# CSS811_CO2_TVOC_Breakout.net
KiCad netlist of a schematic drawn in EAGLE
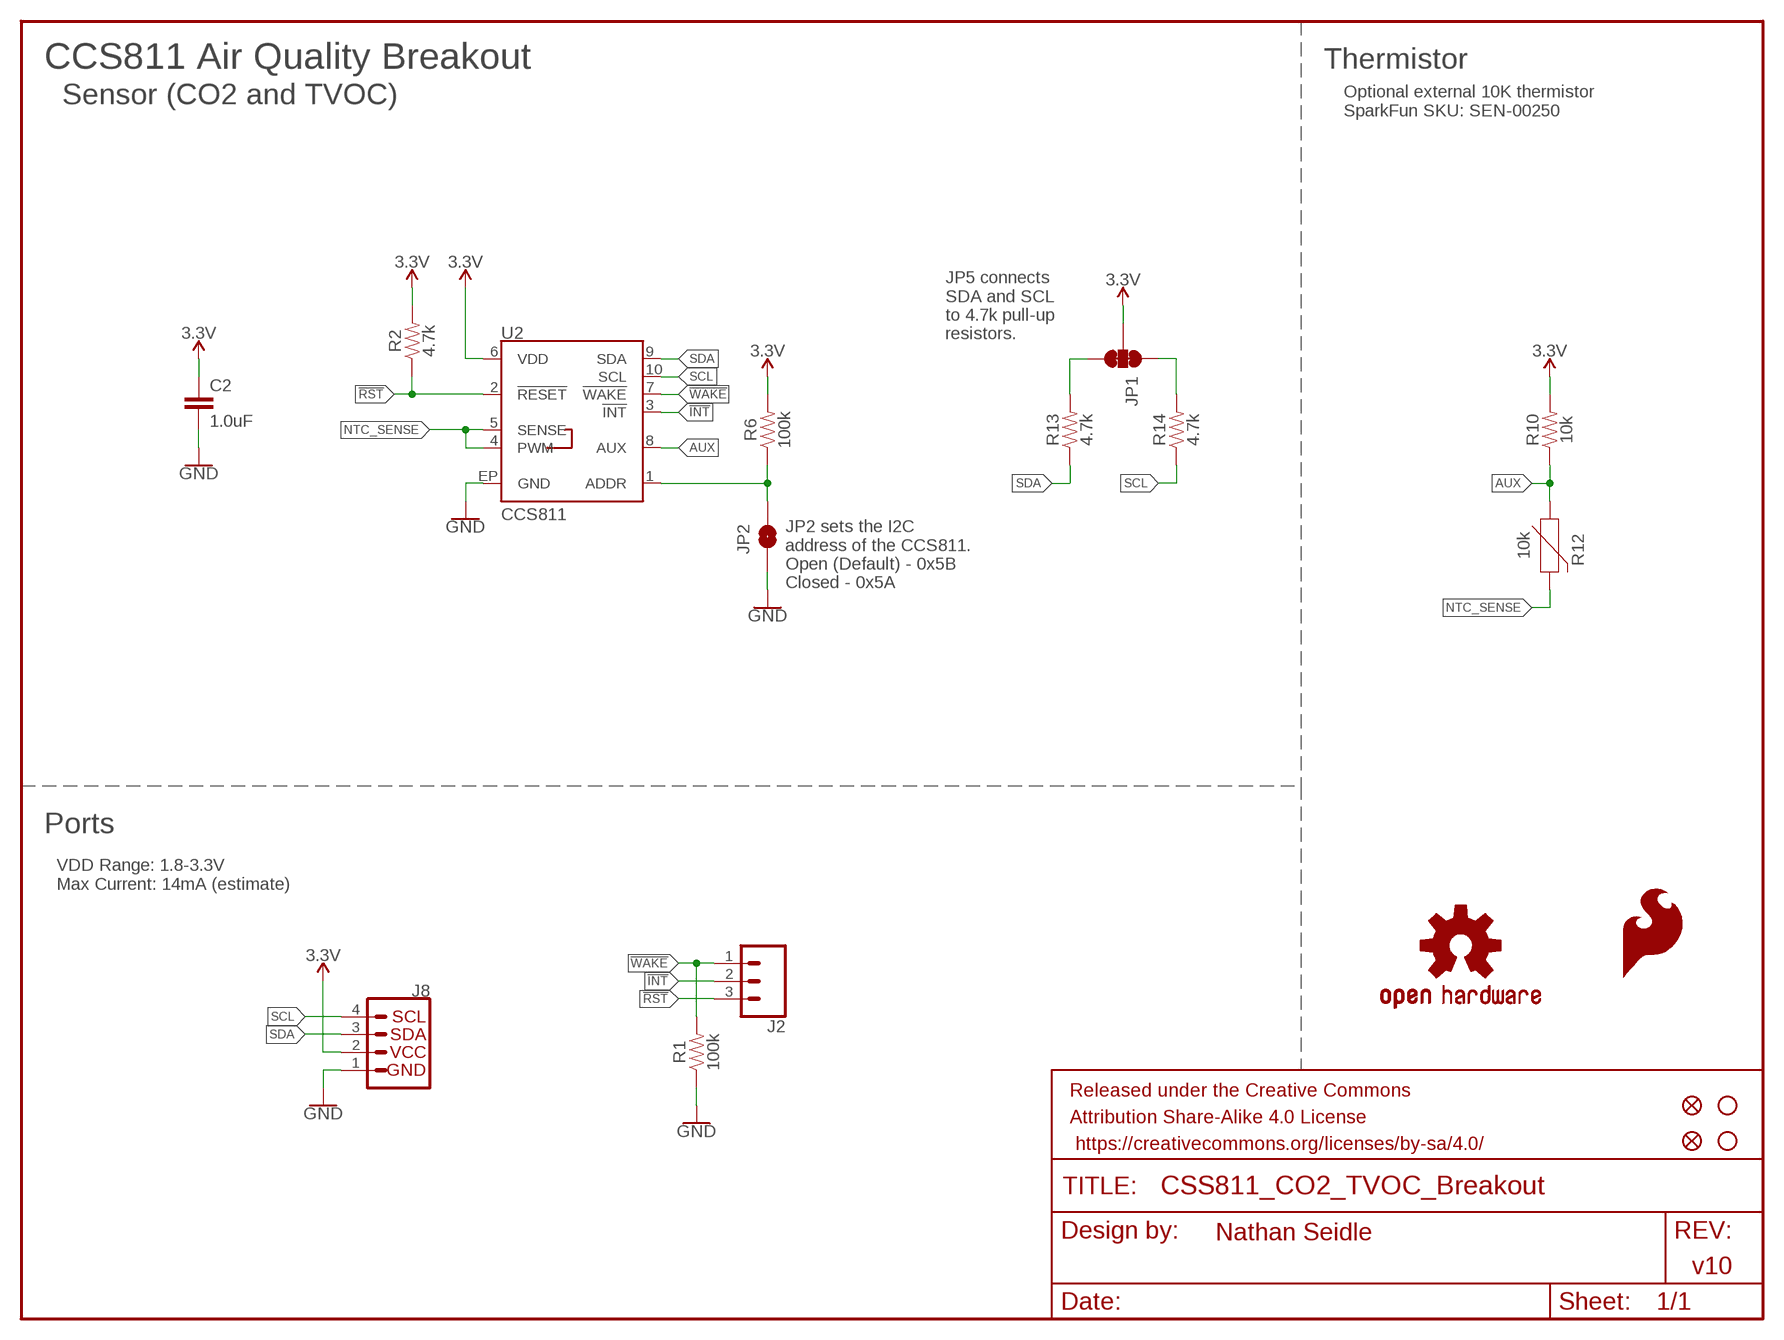
[diagram p0: schematic, sheet 1]

(export (version "E")
  (design (tool "Eeschema 10.0.6"))
  (components
    (comp (ref "C2")
      (value "1.0uF")
      (footprint "eagle-import:0603")
      (libsource (lib "eagle-import") (part "1.0UF-0603-16V-10%"))
    )
    (comp (ref "FD1")
      (value "FIDUCIAL1X2")
      (footprint "eagle-import:FIDUCIAL-1X2")
      (libsource (lib "eagle-import") (part "FIDUCIAL1X2"))
    )
    (comp (ref "FD2")
      (value "FIDUCIAL1X2")
      (footprint "eagle-import:FIDUCIAL-1X2")
      (libsource (lib "eagle-import") (part "FIDUCIAL1X2"))
    )
    (comp (ref "FRAME1")
      (value "FRAME-LETTER")
      (footprint "eagle-import:CREATIVE_COMMONS")
      (libsource (lib "eagle-import") (part "FRAME-LETTER"))
    )
    (comp (ref "H2")
      (value "STAND-OFF")
      (footprint "eagle-import:STAND-OFF")
      (libsource (lib "eagle-import") (part "STAND-OFF"))
    )
    (comp (ref "H4")
      (value "STAND-OFF")
      (footprint "eagle-import:STAND-OFF")
      (libsource (lib "eagle-import") (part "STAND-OFF"))
    )
    (comp (ref "J2")
      (value "CONN_031X03_NO_SILK")
      (footprint "eagle-import:1X03_NO_SILK")
      (libsource (lib "eagle-import") (part "CONN_031X03_NO_SILK"))
    )
    (comp (ref "J8")
      (value "I2C_STANDARD_NO_SILK")
      (footprint "eagle-import:1X04_NO_SILK")
      (libsource (lib "eagle-import") (part "I2C_STANDARD_NO_SILK"))
    )
    (comp (ref "JP1")
      (value "JUMPER-SMT_3_2-NC_TRACE_SILK")
      (footprint "eagle-import:SMT-JUMPER_3_2-NC_TRACE_SILK")
      (libsource (lib "eagle-import") (part "JUMPER-SMT_3_2-NC_TRACE_SILK"))
    )
    (comp (ref "JP2")
      (value "JUMPER-SMT_2_NO_SILK")
      (footprint "eagle-import:SMT-JUMPER_2_NO_SILK")
      (libsource (lib "eagle-import") (part "JUMPER-SMT_2_NO_SILK"))
    )
    (comp (ref "LOGO1")
      (value "SFE_LOGO_FLAME.2_INCH")
      (footprint "eagle-import:SFE_LOGO_FLAME_.2")
      (libsource (lib "eagle-import") (part "SFE_LOGO_FLAME.2_INCH"))
    )
    (comp (ref "LOGO4")
      (value "OSHW-LOGOS")
      (footprint "eagle-import:OSHW-LOGO-S")
      (libsource (lib "eagle-import") (part "OSHW-LOGOS"))
    )
    (comp (ref "R1")
      (value "100k")
      (footprint "eagle-import:0603")
      (libsource (lib "eagle-import") (part "100KOHM-0603-1/10W-1%"))
    )
    (comp (ref "R2")
      (value "4.7k")
      (footprint "eagle-import:0603")
      (libsource (lib "eagle-import") (part "4.7KOHM-0603-1/10W-1%"))
    )
    (comp (ref "R6")
      (value "100k")
      (footprint "eagle-import:0603")
      (libsource (lib "eagle-import") (part "100KOHM-0603-1/10W-1%"))
    )
    (comp (ref "R10")
      (value "10k")
      (footprint "eagle-import:0603")
      (libsource (lib "eagle-import") (part "10KOHM-0603-1/10W-1%"))
    )
    (comp (ref "R12")
      (value "10k")
      (footprint "eagle-import:AXIAL-0.1")
      (fields (field (name "PROD_ID") "N/A"))
      (libsource (lib "eagle-import") (part "NTC-THERMISTOR-AXIAL-0.1"))
    )
    (comp (ref "R13")
      (value "4.7k")
      (footprint "eagle-import:0603")
      (libsource (lib "eagle-import") (part "4.7KOHM-0603-1/10W-1%"))
    )
    (comp (ref "R14")
      (value "4.7k")
      (footprint "eagle-import:0603")
      (libsource (lib "eagle-import") (part "4.7KOHM-0603-1/10W-1%"))
    )
    (comp (ref "U2")
      (value "CCS811")
      (footprint "eagle-import:LGA10")
      (libsource (lib "eagle-import") (part "CCS811"))
    )
  )
  (nets
    (net (code "1") (name "/~{INT}") (class "Default")
      (node (ref "J2") (pin "2") (pinfunction "2_2") (pintype "passive"))
      (node (ref "U2") (pin "3") (pinfunction "~{INT}_3") (pintype "bidirectional"))
    )
    (net (code "2") (name "/~{RST}") (class "Default")
      (node (ref "J2") (pin "3") (pinfunction "3_3") (pintype "passive"))
      (node (ref "R2") (pin "1") (pinfunction "1_1") (pintype "passive"))
      (node (ref "U2") (pin "2") (pinfunction "~{RESET}_2") (pintype "bidirectional"))
    )
    (net (code "3") (name "/~{WAKE}") (class "Default")
      (node (ref "J2") (pin "1") (pinfunction "1_1") (pintype "passive"))
      (node (ref "R1") (pin "2") (pinfunction "2_2") (pintype "passive"))
      (node (ref "U2") (pin "7") (pinfunction "~{WAKE}_7") (pintype "bidirectional"))
    )
    (net (code "4") (name "3.3V") (class "Default")
      (node (ref "C2") (pin "1") (pinfunction "1_1") (pintype "passive"))
      (node (ref "J8") (pin "2") (pinfunction "2_2") (pintype "power_in"))
      (node (ref "JP1") (pin "2") (pinfunction "2_2") (pintype "passive"))
      (node (ref "R10") (pin "2") (pinfunction "2_2") (pintype "passive"))
      (node (ref "R2") (pin "2") (pinfunction "2_2") (pintype "passive"))
      (node (ref "R6") (pin "2") (pinfunction "2_2") (pintype "passive"))
      (node (ref "U2") (pin "6") (pinfunction "VDD_6") (pintype "bidirectional"))
    )
    (net (code "5") (name "AUX") (class "Default")
      (node (ref "R10") (pin "1") (pinfunction "1_1") (pintype "passive"))
      (node (ref "R12") (pin "P$1") (pinfunction "1_P$1") (pintype "bidirectional"))
      (node (ref "U2") (pin "8") (pinfunction "AUX_8") (pintype "bidirectional"))
    )
    (net (code "6") (name "GND") (class "Default")
      (node (ref "C2") (pin "2") (pinfunction "2_2") (pintype "passive"))
      (node (ref "J8") (pin "1") (pinfunction "1_1") (pintype "power_in"))
      (node (ref "JP2") (pin "1") (pinfunction "1_1") (pintype "passive"))
      (node (ref "R1") (pin "1") (pinfunction "1_1") (pintype "passive"))
      (node (ref "U2") (pin "EP") (pinfunction "GND_EP") (pintype "bidirectional"))
    )
    (net (code "7") (name "NTC_SENSE") (class "Default")
      (node (ref "R12") (pin "P$2") (pinfunction "2_P$2") (pintype "bidirectional"))
      (node (ref "U2") (pin "4") (pinfunction "PWM_4") (pintype "bidirectional"))
      (node (ref "U2") (pin "5") (pinfunction "SENSE_5") (pintype "bidirectional"))
    )
    (net (code "8") (name "Net-(JP1-Pad1)") (class "Default")
      (node (ref "JP1") (pin "1") (pinfunction "1_1") (pintype "passive"))
      (node (ref "R14") (pin "2") (pinfunction "2_2") (pintype "passive"))
    )
    (net (code "9") (name "Net-(JP1-Pad3)") (class "Default")
      (node (ref "JP1") (pin "3") (pinfunction "3_3") (pintype "passive"))
      (node (ref "R13") (pin "2") (pinfunction "2_2") (pintype "passive"))
    )
    (net (code "10") (name "Net-(U2-ADDR)") (class "Default")
      (node (ref "JP2") (pin "2") (pinfunction "2_2") (pintype "passive"))
      (node (ref "R6") (pin "1") (pinfunction "1_1") (pintype "passive"))
      (node (ref "U2") (pin "1") (pinfunction "ADDR_1") (pintype "bidirectional"))
    )
    (net (code "11") (name "SCL") (class "Default")
      (node (ref "J8") (pin "4") (pinfunction "4_4") (pintype "passive"))
      (node (ref "R14") (pin "1") (pinfunction "1_1") (pintype "passive"))
      (node (ref "U2") (pin "10") (pinfunction "SCL_10") (pintype "bidirectional"))
    )
    (net (code "12") (name "SDA") (class "Default")
      (node (ref "J8") (pin "3") (pinfunction "3_3") (pintype "passive"))
      (node (ref "R13") (pin "1") (pinfunction "1_1") (pintype "passive"))
      (node (ref "U2") (pin "9") (pinfunction "SDA_9") (pintype "bidirectional"))
    )
  )
)
